# FUNCTION_BUTTONS.net
KiCad netlist of a schematic drawn in Altium Designer
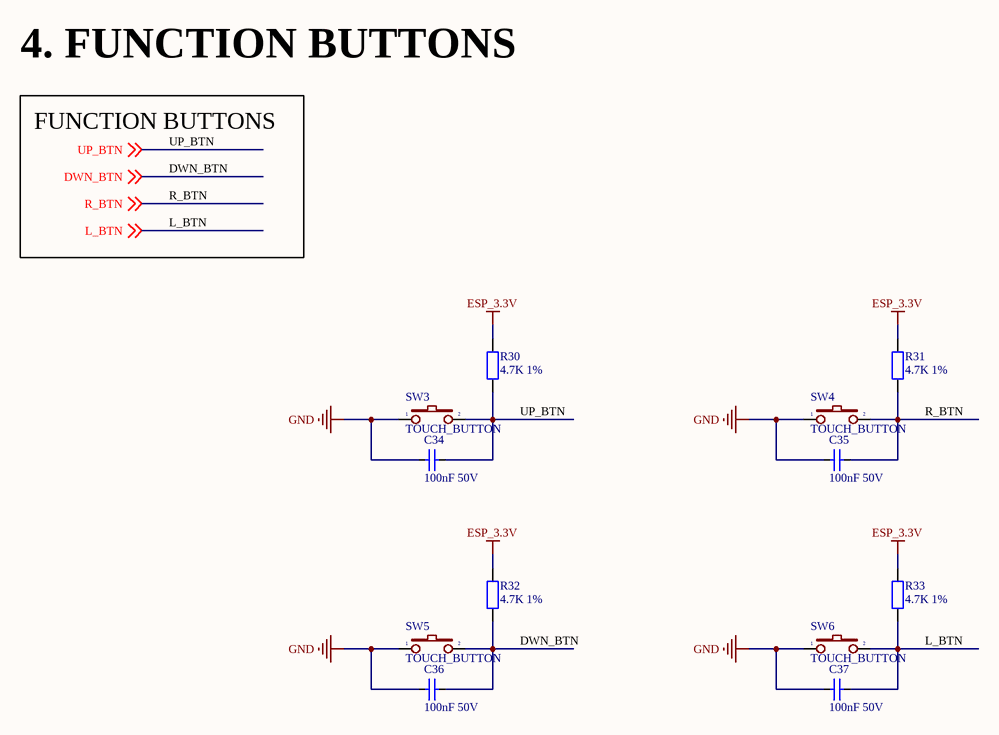
[diagram p0: FUNCTION_BUTTONS.SchDoc]

(export (version "E")
  (design (tool "Eeschema 10.0.6"))
  (components
    (comp (ref "C34")
      (value "100nF 50V")
      (footprint "CAP_SMD_0603")
      (description "0.1 µF ±10% 50V Ceramic Capacitor X7R 0603 (1608 Metric)")
      (fields
        (field (name "MANUFACTURER") "Samsung Electro-Mechanics")
        (field (name "MANUFACTURE PART NUMBER") "CL10B104KB8NNNC")
      )
      (libsource (lib "Capacitors") (part "C0603_MLCC_100nF_50V"))
    )
    (comp (ref "C35")
      (value "100nF 50V")
      (footprint "CAP_SMD_0603")
      (description "0.1 µF ±10% 50V Ceramic Capacitor X7R 0603 (1608 Metric)")
      (fields
        (field (name "MANUFACTURER") "Samsung Electro-Mechanics")
        (field (name "MANUFACTURE PART NUMBER") "CL10B104KB8NNNC")
      )
      (libsource (lib "Capacitors") (part "C0603_MLCC_100nF_50V"))
    )
    (comp (ref "C36")
      (value "100nF 50V")
      (footprint "CAP_SMD_0603")
      (description "0.1 µF ±10% 50V Ceramic Capacitor X7R 0603 (1608 Metric)")
      (fields
        (field (name "MANUFACTURER") "Samsung Electro-Mechanics")
        (field (name "MANUFACTURE PART NUMBER") "CL10B104KB8NNNC")
      )
      (libsource (lib "Capacitors") (part "C0603_MLCC_100nF_50V"))
    )
    (comp (ref "C37")
      (value "100nF 50V")
      (footprint "CAP_SMD_0603")
      (description "0.1 µF ±10% 50V Ceramic Capacitor X7R 0603 (1608 Metric)")
      (fields
        (field (name "MANUFACTURER") "Samsung Electro-Mechanics")
        (field (name "MANUFACTURE PART NUMBER") "CL10B104KB8NNNC")
      )
      (libsource (lib "Capacitors") (part "C0603_MLCC_100nF_50V"))
    )
    (comp (ref "R30")
      (value "4.7K 1%")
      (footprint "RES_SMD_0603")
      (description "4.7 kOhms ±1% 0.1W, 1/10W Chip Resistor 0603 (1608 Metric) Moisture Resistant Thick Film")
      (fields
        (field (name "MANUFACTURER") "YAGEO")
        (field (name "MANUFACTURE PART NUMBER") "RC0603FR-074K7L")
      )
      (libsource (lib "Resistors") (part "R0603_4.7K"))
    )
    (comp (ref "R31")
      (value "4.7K 1%")
      (footprint "RES_SMD_0603")
      (description "4.7 kOhms ±1% 0.1W, 1/10W Chip Resistor 0603 (1608 Metric) Moisture Resistant Thick Film")
      (fields
        (field (name "MANUFACTURER") "YAGEO")
        (field (name "MANUFACTURE PART NUMBER") "RC0603FR-074K7L")
      )
      (libsource (lib "Resistors") (part "R0603_4.7K"))
    )
    (comp (ref "R32")
      (value "4.7K 1%")
      (footprint "RES_SMD_0603")
      (description "4.7 kOhms ±1% 0.1W, 1/10W Chip Resistor 0603 (1608 Metric) Moisture Resistant Thick Film")
      (fields
        (field (name "MANUFACTURER") "YAGEO")
        (field (name "MANUFACTURE PART NUMBER") "RC0603FR-074K7L")
      )
      (libsource (lib "Resistors") (part "R0603_4.7K"))
    )
    (comp (ref "R33")
      (value "4.7K 1%")
      (footprint "RES_SMD_0603")
      (description "4.7 kOhms ±1% 0.1W, 1/10W Chip Resistor 0603 (1608 Metric) Moisture Resistant Thick Film")
      (fields
        (field (name "MANUFACTURER") "YAGEO")
        (field (name "MANUFACTURE PART NUMBER") "RC0603FR-074K7L")
      )
      (libsource (lib "Resistors") (part "R0603_4.7K"))
    )
    (comp (ref "SW3")
      (value "TOUCH_BUTTON")
      (footprint "TOUCH_BUTTON")
      (libsource (lib "Button") (part "TOUCH_BUTTON"))
    )
    (comp (ref "SW4")
      (value "TOUCH_BUTTON")
      (footprint "TOUCH_BUTTON")
      (libsource (lib "Button") (part "TOUCH_BUTTON"))
    )
    (comp (ref "SW5")
      (value "TOUCH_BUTTON")
      (footprint "TOUCH_BUTTON")
      (libsource (lib "Button") (part "TOUCH_BUTTON"))
    )
    (comp (ref "SW6")
      (value "TOUCH_BUTTON")
      (footprint "TOUCH_BUTTON")
      (libsource (lib "Button") (part "TOUCH_BUTTON"))
    )
  )
  (nets
    (net (code "1") (name "DWN_BTN") (class "Default")
      (node (ref "C36") (pin "2") (pinfunction "2_2") (pintype "passive"))
      (node (ref "R32") (pin "1") (pinfunction "1_1") (pintype "passive"))
      (node (ref "SW5") (pin "2") (pinfunction "2_2") (pintype "passive"))
    )
    (net (code "2") (name "ESP_3.3V") (class "Default")
      (node (ref "R30") (pin "2") (pinfunction "2_2") (pintype "passive"))
      (node (ref "R31") (pin "2") (pinfunction "2_2") (pintype "passive"))
      (node (ref "R32") (pin "2") (pinfunction "2_2") (pintype "passive"))
      (node (ref "R33") (pin "2") (pinfunction "2_2") (pintype "passive"))
    )
    (net (code "3") (name "GND") (class "Default")
      (node (ref "C34") (pin "1") (pinfunction "1_1") (pintype "passive"))
      (node (ref "C35") (pin "1") (pinfunction "1_1") (pintype "passive"))
      (node (ref "C36") (pin "1") (pinfunction "1_1") (pintype "passive"))
      (node (ref "C37") (pin "1") (pinfunction "1_1") (pintype "passive"))
      (node (ref "SW3") (pin "1") (pinfunction "1_1") (pintype "passive"))
      (node (ref "SW4") (pin "1") (pinfunction "1_1") (pintype "passive"))
      (node (ref "SW5") (pin "1") (pinfunction "1_1") (pintype "passive"))
      (node (ref "SW6") (pin "1") (pinfunction "1_1") (pintype "passive"))
    )
    (net (code "4") (name "L_BTN") (class "Default")
      (node (ref "C37") (pin "2") (pinfunction "2_2") (pintype "passive"))
      (node (ref "R33") (pin "1") (pinfunction "1_1") (pintype "passive"))
      (node (ref "SW6") (pin "2") (pinfunction "2_2") (pintype "passive"))
    )
    (net (code "5") (name "R_BTN") (class "Default")
      (node (ref "C35") (pin "2") (pinfunction "2_2") (pintype "passive"))
      (node (ref "R31") (pin "1") (pinfunction "1_1") (pintype "passive"))
      (node (ref "SW4") (pin "2") (pinfunction "2_2") (pintype "passive"))
    )
    (net (code "6") (name "UP_BTN") (class "Default")
      (node (ref "C34") (pin "2") (pinfunction "2_2") (pintype "passive"))
      (node (ref "R30") (pin "1") (pinfunction "1_1") (pintype "passive"))
      (node (ref "SW3") (pin "2") (pinfunction "2_2") (pintype "passive"))
    )
  )
)
